# usb_qc.net
KiCad netlist of a schematic drawn in EAGLE
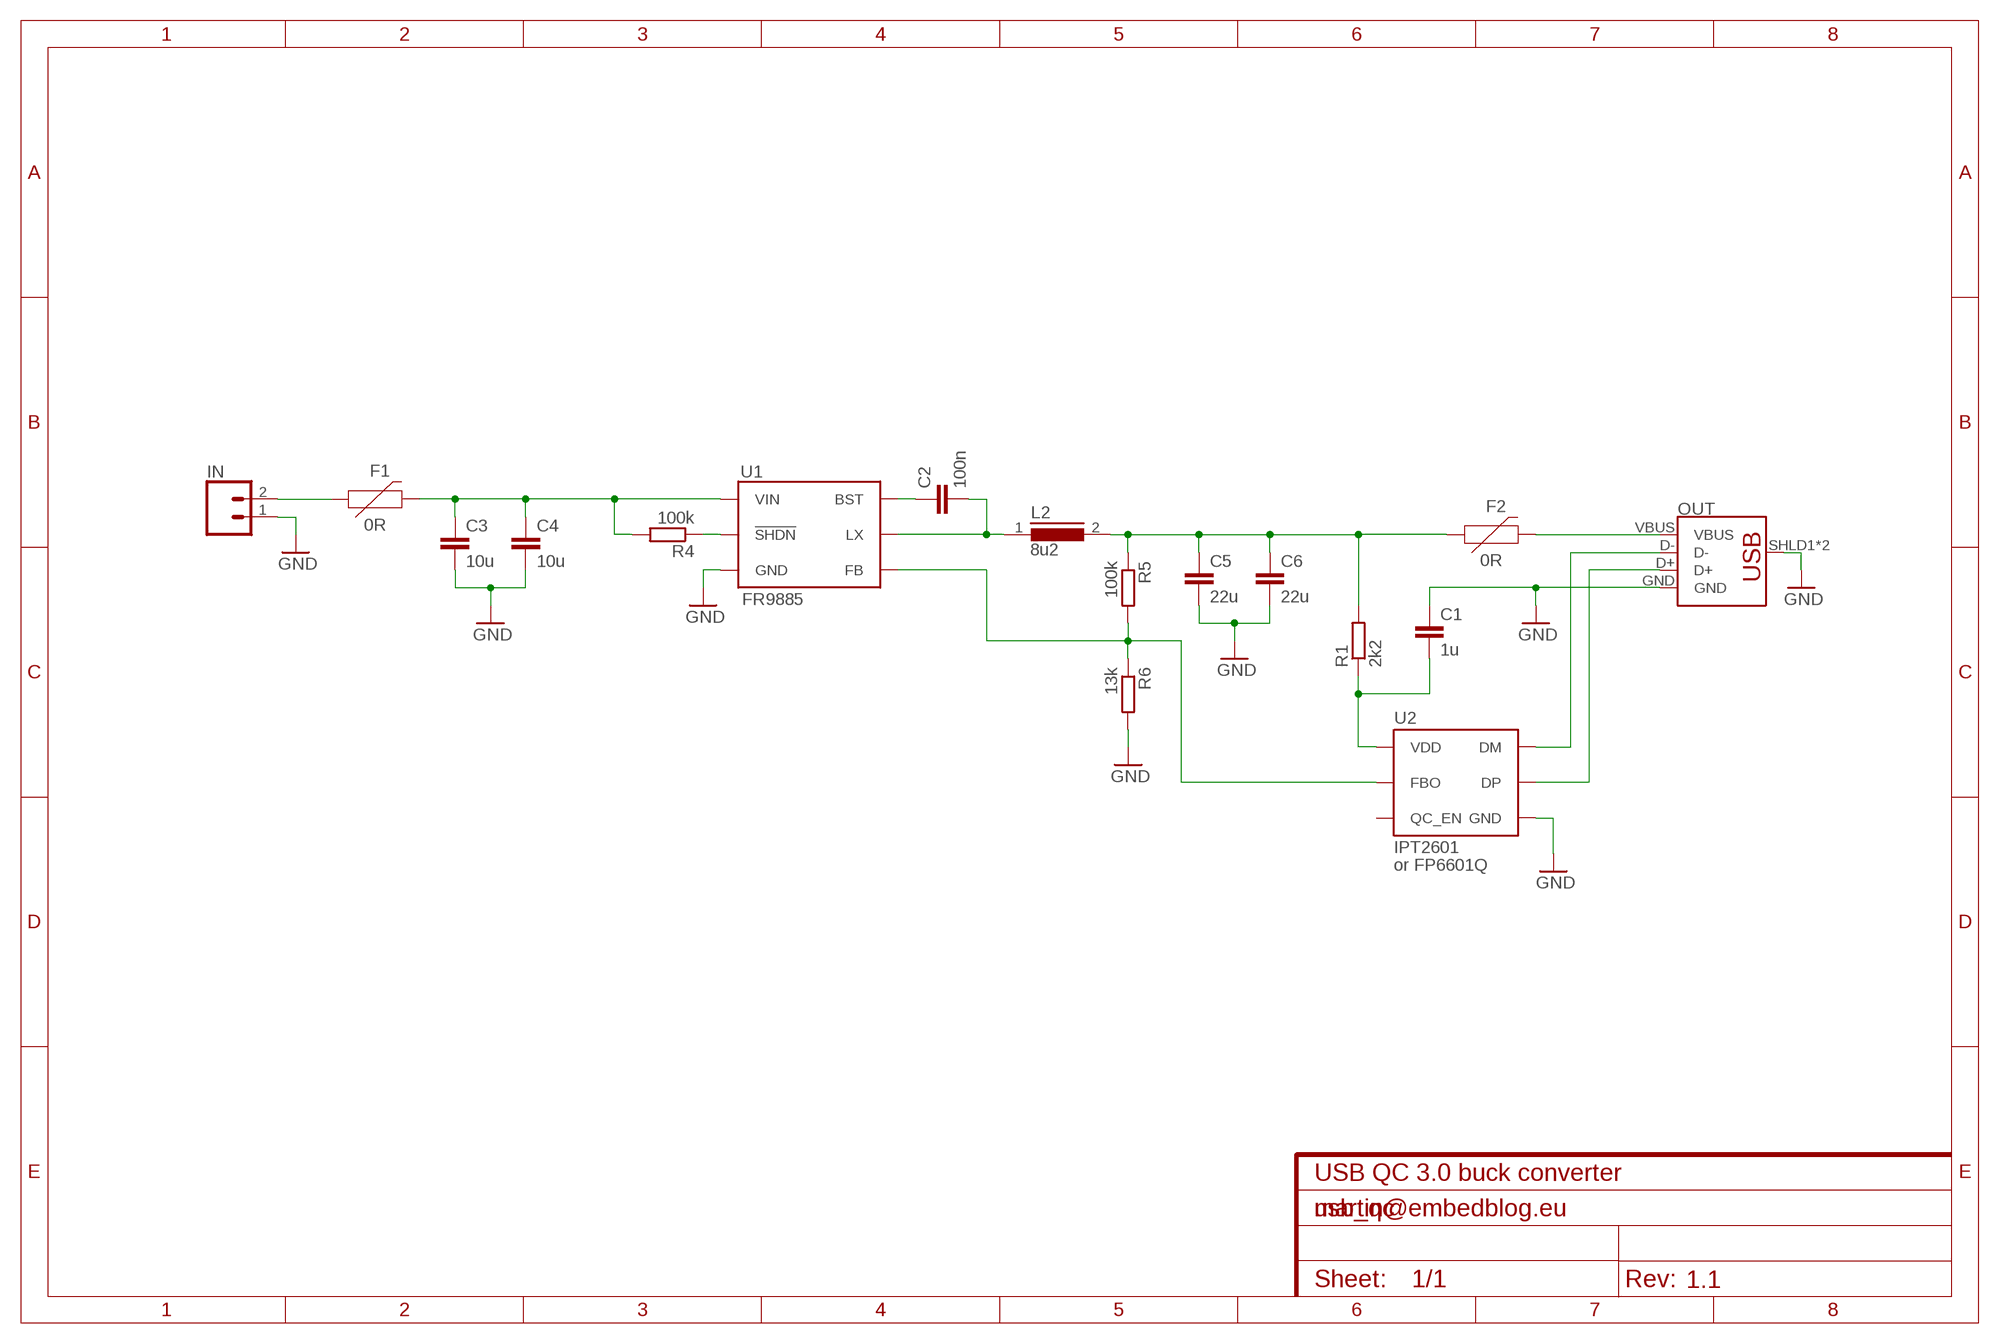
[diagram p0: schematic, sheet 1]

(export (version "E")
  (design (tool "Eeschema 10.0.6"))
  (components
    (comp (ref "C1")
      (value "1u")
      (footprint "eagle-import:C1206")
      (libsource (lib "eagle-import") (part "C-EUC1206"))
    )
    (comp (ref "C2")
      (value "100n")
      (footprint "eagle-import:C1206")
      (libsource (lib "eagle-import") (part "C-EUC1206"))
    )
    (comp (ref "C3")
      (value "10u")
      (footprint "eagle-import:C1206")
      (libsource (lib "eagle-import") (part "C-EUC1206"))
    )
    (comp (ref "C4")
      (value "10u")
      (footprint "eagle-import:C1206")
      (libsource (lib "eagle-import") (part "C-EUC1206"))
    )
    (comp (ref "C5")
      (value "22u")
      (footprint "eagle-import:C1206")
      (libsource (lib "eagle-import") (part "C-EUC1206"))
    )
    (comp (ref "C6")
      (value "22u")
      (footprint "eagle-import:C1206")
      (libsource (lib "eagle-import") (part "C-EUC1206"))
    )
    (comp (ref "F1")
      (value "0R")
      (footprint "eagle-import:1206")
      (libsource (lib "eagle-import") (part "PPTC_HALF-AMP"))
    )
    (comp (ref "F2")
      (value "0R")
      (footprint "eagle-import:1206")
      (libsource (lib "eagle-import") (part "PPTC_HALF-AMP"))
    )
    (comp (ref "IN")
      (value "5MM_SCREWTERMINAL_LARGE")
      (footprint "eagle-import:SCREWTERMINAL-5MM-2")
      (libsource (lib "eagle-import") (part "5MM_SCREWTERMINAL_LARGE"))
    )
    (comp (ref "L2")
      (value "8u2")
      (footprint "eagle-import:DR73")
      (libsource (lib "eagle-import") (part "DR73"))
    )
    (comp (ref "OUT")
      (value "USB_A_REVERSED")
      (footprint "eagle-import:USB-A-S-SILK-FEMALE")
      (libsource (lib "eagle-import") (part "USB_A_REVERSED"))
    )
    (comp (ref "R1")
      (value "2k2")
      (footprint "eagle-import:R1206")
      (libsource (lib "eagle-import") (part "R-EU_R1206"))
    )
    (comp (ref "R4")
      (value "100k")
      (footprint "eagle-import:R1206")
      (libsource (lib "eagle-import") (part "R-EU_R1206"))
    )
    (comp (ref "R5")
      (value "100k")
      (footprint "eagle-import:R1206")
      (libsource (lib "eagle-import") (part "R-EU_R1206"))
    )
    (comp (ref "R6")
      (value "13k")
      (footprint "eagle-import:R1206")
      (libsource (lib "eagle-import") (part "R-EU_R1206"))
    )
    (comp (ref "U1")
      (value "FR9885")
      (footprint "eagle-import:SOT23-6")
      (libsource (lib "eagle-import") (part "FR9885"))
    )
    (comp (ref "U2")
      (value "IPT2601")
      (footprint "eagle-import:SOT23-6")
      (libsource (lib "eagle-import") (part "IPT2601"))
    )
  )
  (nets
    (net (code "1") (name "GND") (class "Default")
      (node (ref "C1") (pin "1") (pinfunction "1_1") (pintype "passive"))
      (node (ref "C3") (pin "2") (pinfunction "2_2") (pintype "passive"))
      (node (ref "C4") (pin "2") (pinfunction "2_2") (pintype "passive"))
      (node (ref "C5") (pin "2") (pinfunction "2_2") (pintype "passive"))
      (node (ref "C6") (pin "2") (pinfunction "2_2") (pintype "passive"))
      (node (ref "IN") (pin "1") (pinfunction "1_1") (pintype "passive"))
      (node (ref "OUT") (pin "GND") (pinfunction "GND_GND") (pintype "power_in"))
      (node (ref "OUT") (pin "SHLD1") (pinfunction "SHIELD_SHLD1") (pintype "bidirectional"))
      (node (ref "OUT") (pin "SHLD2") (pinfunction "SHIELD_SHLD2") (pintype "bidirectional"))
      (node (ref "R6") (pin "2") (pinfunction "2_2") (pintype "passive"))
      (node (ref "U1") (pin "2") (pinfunction "GND_2") (pintype "bidirectional"))
      (node (ref "U2") (pin "2") (pinfunction "GND_2") (pintype "bidirectional"))
    )
    (net (code "2") (name "Net-(C5-Pad1)") (class "Default")
      (node (ref "C5") (pin "1") (pinfunction "1_1") (pintype "passive"))
      (node (ref "C6") (pin "1") (pinfunction "1_1") (pintype "passive"))
      (node (ref "F2") (pin "1") (pinfunction "1_1") (pintype "bidirectional"))
      (node (ref "L2") (pin "2") (pinfunction "2_2") (pintype "passive"))
      (node (ref "R1") (pin "2") (pinfunction "2_2") (pintype "passive"))
      (node (ref "R5") (pin "1") (pinfunction "1_1") (pintype "passive"))
    )
    (net (code "3") (name "Net-(F1-Pad1)") (class "Default")
      (node (ref "F1") (pin "1") (pinfunction "1_1") (pintype "bidirectional"))
      (node (ref "IN") (pin "2") (pinfunction "2_2") (pintype "passive"))
    )
    (net (code "4") (name "Net-(F2-Pad2)") (class "Default")
      (node (ref "F2") (pin "2") (pinfunction "2_2") (pintype "bidirectional"))
      (node (ref "OUT") (pin "VBUS") (pinfunction "VBUS_VBUS") (pintype "power_in"))
    )
    (net (code "5") (name "Net-(U1-BST)") (class "Default")
      (node (ref "C2") (pin "1") (pinfunction "1_1") (pintype "passive"))
      (node (ref "U1") (pin "1") (pinfunction "BST_1") (pintype "bidirectional"))
    )
    (net (code "6") (name "Net-(U1-FB)") (class "Default")
      (node (ref "R5") (pin "2") (pinfunction "2_2") (pintype "passive"))
      (node (ref "R6") (pin "1") (pinfunction "1_1") (pintype "passive"))
      (node (ref "U1") (pin "3") (pinfunction "FB_3") (pintype "bidirectional"))
      (node (ref "U2") (pin "3") (pinfunction "FBO_3") (pintype "bidirectional"))
    )
    (net (code "7") (name "Net-(U1-LX)") (class "Default")
      (node (ref "C2") (pin "2") (pinfunction "2_2") (pintype "passive"))
      (node (ref "L2") (pin "1") (pinfunction "1_1") (pintype "passive"))
      (node (ref "U1") (pin "6") (pinfunction "LX_6") (pintype "bidirectional"))
    )
    (net (code "8") (name "Net-(U1-VIN)") (class "Default")
      (node (ref "C3") (pin "1") (pinfunction "1_1") (pintype "passive"))
      (node (ref "C4") (pin "1") (pinfunction "1_1") (pintype "passive"))
      (node (ref "F1") (pin "2") (pinfunction "2_2") (pintype "bidirectional"))
      (node (ref "R4") (pin "2") (pinfunction "2_2") (pintype "passive"))
      (node (ref "U1") (pin "5") (pinfunction "VIN_5") (pintype "bidirectional"))
    )
    (net (code "9") (name "Net-(U1-~{SHDN})") (class "Default")
      (node (ref "R4") (pin "1") (pinfunction "1_1") (pintype "passive"))
      (node (ref "U1") (pin "4") (pinfunction "~{SHDN}_4") (pintype "bidirectional"))
    )
    (net (code "10") (name "Net-(U2-DM)") (class "Default")
      (node (ref "OUT") (pin "D-") (pinfunction "D-_D-") (pintype "bidirectional"))
      (node (ref "U2") (pin "6") (pinfunction "DM_6") (pintype "bidirectional"))
    )
    (net (code "11") (name "Net-(U2-DP)") (class "Default")
      (node (ref "OUT") (pin "D+") (pinfunction "D+_D+") (pintype "bidirectional"))
      (node (ref "U2") (pin "1") (pinfunction "DP_1") (pintype "bidirectional"))
    )
    (net (code "12") (name "Net-(U2-VDD)") (class "Default")
      (node (ref "C1") (pin "2") (pinfunction "2_2") (pintype "passive"))
      (node (ref "R1") (pin "1") (pinfunction "1_1") (pintype "passive"))
      (node (ref "U2") (pin "5") (pinfunction "VDD_5") (pintype "bidirectional"))
    )
    (net (code "13") (name "unconnected-(U2-QC_EN-Pad4)") (class "Default")
      (node (ref "U2") (pin "4") (pinfunction "QC_EN_4") (pintype "bidirectional"))
    )
  )
)
